# eeprom.net
KiCad netlist of a schematic drawn in EAGLE
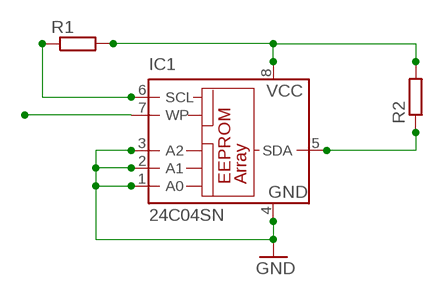
[diagram p0: schematic, sheet 1]

(export (version "E")
  (design (tool "Eeschema 10.0.6"))
  (components
    (comp (ref "IC1")
      (value "24C04SN")
      (footprint "eagle-import:SO-08")
      (fields (field (name "MPN") "M24C04-WMN6P"))
      (libsource (lib "eagle-import") (part "24CSN04"))
    )
    (comp (ref "R1")
      (value "R-EU_R2012W")
      (footprint "eagle-import:R2012W")
      (libsource (lib "eagle-import") (part "R-EU_R2012W"))
    )
    (comp (ref "R2")
      (value "R-EU_R2012W")
      (footprint "eagle-import:R2012W")
      (libsource (lib "eagle-import") (part "R-EU_R2012W"))
    )
  )
  (nets
    (net (code "1") (name "GND") (class "Default")
      (node (ref "IC1") (pin "1") (pinfunction "A0_1") (pintype "input"))
      (node (ref "IC1") (pin "2") (pinfunction "A1_2") (pintype "input"))
      (node (ref "IC1") (pin "3") (pinfunction "A2_3") (pintype "input"))
      (node (ref "IC1") (pin "4") (pinfunction "GND_4") (pintype "power_in"))
    )
    (net (code "2") (name "Net-(IC1-SCL)") (class "Default")
      (node (ref "IC1") (pin "6") (pinfunction "SCL_6") (pintype "input"))
      (node (ref "R1") (pin "1") (pinfunction "1_1") (pintype "passive"))
    )
    (net (code "3") (name "Net-(IC1-SDA)") (class "Default")
      (node (ref "IC1") (pin "5") (pinfunction "SDA_5") (pintype "bidirectional"))
      (node (ref "R2") (pin "1") (pinfunction "1_1") (pintype "passive"))
    )
    (net (code "4") (name "Net-(IC1-VCC)") (class "Default")
      (node (ref "IC1") (pin "8") (pinfunction "VCC_8") (pintype "power_in"))
      (node (ref "R1") (pin "2") (pinfunction "2_2") (pintype "passive"))
      (node (ref "R2") (pin "2") (pinfunction "2_2") (pintype "passive"))
    )
    (net (code "5") (name "unconnected-(IC1-WP-Pad7)") (class "Default")
      (node (ref "IC1") (pin "7") (pinfunction "WP_7") (pintype "input"))
    )
  )
)
